# ProjV1.net
KiCad netlist of a schematic drawn in EAGLE
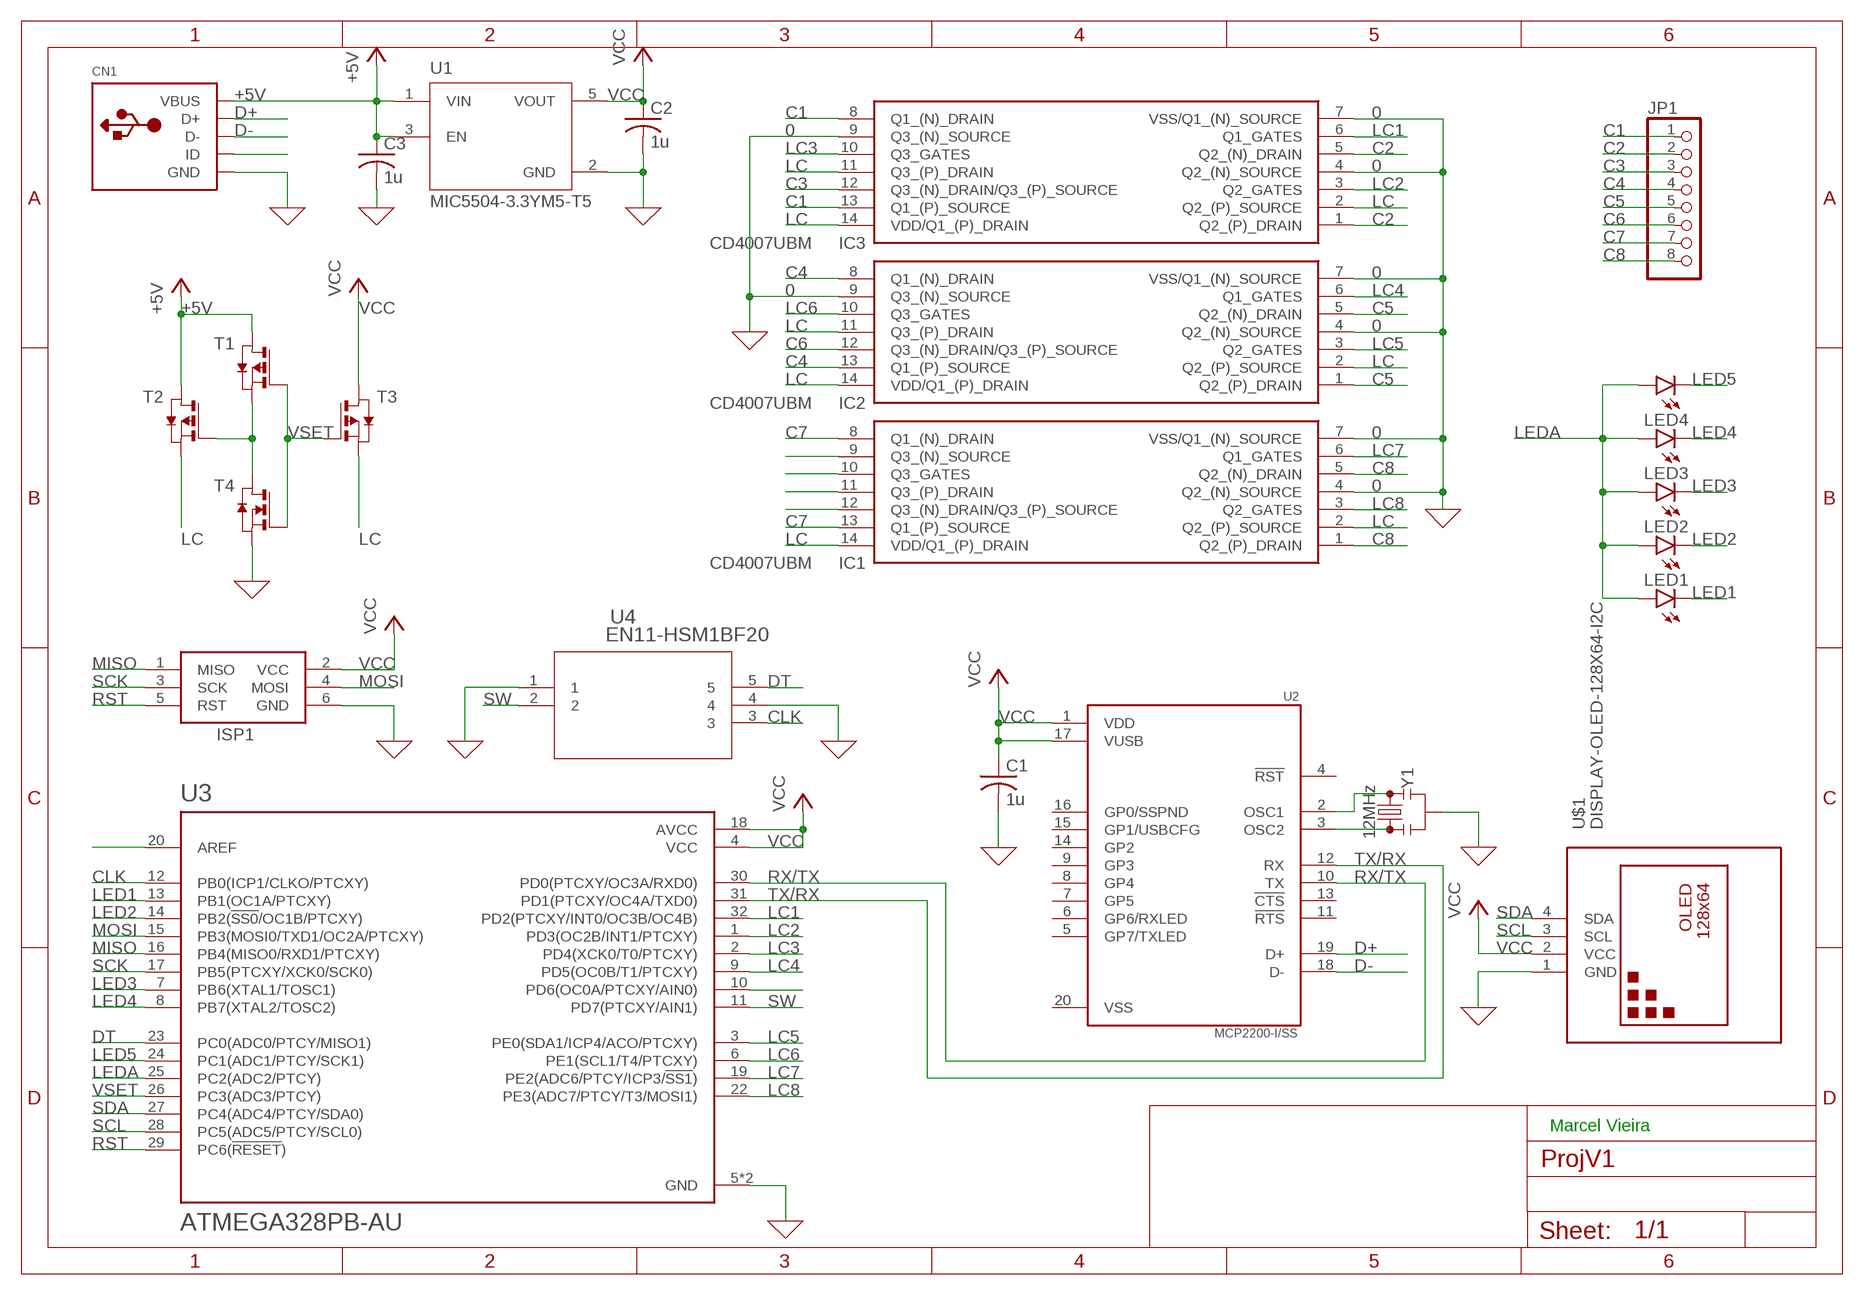
[diagram p0: schematic, sheet 1]

(export (version "E")
  (design (tool "Eeschema 10.0.6"))
  (components
    (comp (ref "C1")
      (value "1u")
      (footprint "eagle-import:C0805")
      (libsource (lib "eagle-import") (part "C-USC0805"))
    )
    (comp (ref "C2")
      (value "1u")
      (footprint "eagle-import:C0805")
      (libsource (lib "eagle-import") (part "C-USC0805"))
    )
    (comp (ref "C3")
      (value "1u")
      (footprint "eagle-import:C0805")
      (libsource (lib "eagle-import") (part "C-USC0805"))
    )
    (comp (ref "CN1")
      (value "USBMINIB")
      (footprint "eagle-import:USB-MINIB")
      (libsource (lib "eagle-import") (part "USBMINIB"))
    )
    (comp (ref "IC1")
      (value "CD4007UBM")
      (footprint "eagle-import:SOIC127P600X175-14N")
      (fields (field (name "MOUSER_PART_NUMBER") "595-CD4007UBM"))
      (libsource (lib "eagle-import") (part "CD4007UBM"))
    )
    (comp (ref "IC2")
      (value "CD4007UBM")
      (footprint "eagle-import:SOIC127P600X175-14N")
      (fields (field (name "MOUSER_PART_NUMBER") "595-CD4007UBM"))
      (libsource (lib "eagle-import") (part "CD4007UBM"))
    )
    (comp (ref "IC3")
      (value "CD4007UBM")
      (footprint "eagle-import:SOIC127P600X175-14N")
      (fields (field (name "MOUSER_PART_NUMBER") "595-CD4007UBM"))
      (libsource (lib "eagle-import") (part "CD4007UBM"))
    )
    (comp (ref "ISP1")
      (value "AVRISP-6")
      (footprint "eagle-import:AVRISP")
      (libsource (lib "eagle-import") (part "AVRISP-6"))
    )
    (comp (ref "JP1")
      (value "PINHD-1X8-3.5MM")
      (footprint "eagle-import:1X08-3.5MM")
      (libsource (lib "eagle-import") (part "PINHD-1X8-3.5MM"))
    )
    (comp (ref "LED1")
      (value "LEDCHIP-LED0805")
      (footprint "eagle-import:CHIP-LED0805")
      (libsource (lib "eagle-import") (part "LEDCHIP-LED0805"))
    )
    (comp (ref "LED2")
      (value "LEDCHIP-LED0805")
      (footprint "eagle-import:CHIP-LED0805")
      (libsource (lib "eagle-import") (part "LEDCHIP-LED0805"))
    )
    (comp (ref "LED3")
      (value "LEDCHIP-LED0805")
      (footprint "eagle-import:CHIP-LED0805")
      (libsource (lib "eagle-import") (part "LEDCHIP-LED0805"))
    )
    (comp (ref "LED4")
      (value "LEDCHIP-LED0805")
      (footprint "eagle-import:CHIP-LED0805")
      (libsource (lib "eagle-import") (part "LEDCHIP-LED0805"))
    )
    (comp (ref "LED5")
      (value "LEDCHIP-LED0805")
      (footprint "eagle-import:CHIP-LED0805")
      (libsource (lib "eagle-import") (part "LEDCHIP-LED0805"))
    )
    (comp (ref "T1")
      (value "PMOSSOT23")
      (footprint "eagle-import:SOT-23")
      (libsource (lib "eagle-import") (part "PMOSSOT23"))
    )
    (comp (ref "T2")
      (value "PMOSSOT23")
      (footprint "eagle-import:SOT-23")
      (libsource (lib "eagle-import") (part "PMOSSOT23"))
    )
    (comp (ref "T3")
      (value "PMOSSOT23")
      (footprint "eagle-import:SOT-23")
      (libsource (lib "eagle-import") (part "PMOSSOT23"))
    )
    (comp (ref "T4")
      (value "NMOSSOT23")
      (footprint "eagle-import:SOT-23")
      (libsource (lib "eagle-import") (part "NMOSSOT23"))
    )
    (comp (ref "U$1")
      (value "DISPLAY-OLED-128X64-I2C")
      (footprint "eagle-import:DISPLAY-OLED-128X64-I2C")
      (libsource (lib "eagle-import") (part "DISPLAY-OLED-128X64-I2C"))
    )
    (comp (ref "U1")
      (value "MIC5504-3.3YM5-T5")
      (footprint "eagle-import:SOT95P280X145-5N")
      (fields (field (name "MF") "Microchip"))
      (libsource (lib "eagle-import") (part "MIC5504-3.3YM5-T5"))
    )
    (comp (ref "U2")
      (value "MCP2200-I/SS")
      (footprint "eagle-import:SOP65P780X200-20N")
      (fields (field (name "MF") "Microchip"))
      (libsource (lib "eagle-import") (part "MCP2200-I/SS"))
    )
    (comp (ref "U3")
      (value "ATMEGA328PB-AU")
      (footprint "eagle-import:QFP80P900X900X120-32N")
      (fields (field (name "MF") "Microchip Technology / Atmel"))
      (libsource (lib "eagle-import") (part "ATMEGA328PB-AU"))
    )
    (comp (ref "U4")
      (value "EN11-HSM1BF20")
      (footprint "eagle-import:EN11-HSM_TTE")
      (libsource (lib "eagle-import") (part "EN11-HSM1BF20"))
    )
    (comp (ref "Y1")
      (value "12MHz")
      (footprint "eagle-import:RESONATOR-SMD-3.2X1.3")
      (libsource (lib "eagle-import") (part "RESONATOR-16MHZSMD_3.2X1.3"))
    )
  )
  (nets
    (net (code "1") (name "+5V") (class "Default")
      (node (ref "C3") (pin "1") (pinfunction "1_1") (pintype "passive"))
      (node (ref "CN1") (pin "VBUS") (pinfunction "VBUS_VBUS") (pintype "power_in"))
      (node (ref "T1") (pin "1") (pinfunction "D_1") (pintype "passive"))
      (node (ref "T2") (pin "1") (pinfunction "D_1") (pintype "passive"))
      (node (ref "U1") (pin "1") (pinfunction "VIN_1") (pintype "input"))
      (node (ref "U1") (pin "3") (pinfunction "EN_3") (pintype "input"))
    )
    (net (code "2") (name "/C1") (class "Default")
      (node (ref "IC3") (pin "13") (pinfunction "Q1_(P)_SOURCE_13") (pintype "bidirectional"))
      (node (ref "IC3") (pin "8") (pinfunction "Q1_(N)_DRAIN_8") (pintype "bidirectional"))
      (node (ref "JP1") (pin "1") (pinfunction "1_1") (pintype "passive"))
    )
    (net (code "3") (name "/C2") (class "Default")
      (node (ref "IC3") (pin "1") (pinfunction "Q2_(P)_DRAIN_1") (pintype "bidirectional"))
      (node (ref "IC3") (pin "5") (pinfunction "Q2_(N)_DRAIN_5") (pintype "bidirectional"))
      (node (ref "JP1") (pin "2") (pinfunction "2_2") (pintype "passive"))
    )
    (net (code "4") (name "/C3") (class "Default")
      (node (ref "IC3") (pin "12") (pinfunction "Q3_(N)_DRAIN/Q3_(P)_SOURCE_12") (pintype "bidirectional"))
      (node (ref "JP1") (pin "3") (pinfunction "3_3") (pintype "passive"))
    )
    (net (code "5") (name "/C4") (class "Default")
      (node (ref "IC2") (pin "13") (pinfunction "Q1_(P)_SOURCE_13") (pintype "bidirectional"))
      (node (ref "IC2") (pin "8") (pinfunction "Q1_(N)_DRAIN_8") (pintype "bidirectional"))
      (node (ref "JP1") (pin "4") (pinfunction "4_4") (pintype "passive"))
    )
    (net (code "6") (name "/C5") (class "Default")
      (node (ref "IC2") (pin "1") (pinfunction "Q2_(P)_DRAIN_1") (pintype "bidirectional"))
      (node (ref "IC2") (pin "5") (pinfunction "Q2_(N)_DRAIN_5") (pintype "bidirectional"))
      (node (ref "JP1") (pin "5") (pinfunction "5_5") (pintype "passive"))
    )
    (net (code "7") (name "/C6") (class "Default")
      (node (ref "IC2") (pin "12") (pinfunction "Q3_(N)_DRAIN/Q3_(P)_SOURCE_12") (pintype "bidirectional"))
      (node (ref "JP1") (pin "6") (pinfunction "6_6") (pintype "passive"))
    )
    (net (code "8") (name "/C7") (class "Default")
      (node (ref "IC1") (pin "13") (pinfunction "Q1_(P)_SOURCE_13") (pintype "bidirectional"))
      (node (ref "IC1") (pin "8") (pinfunction "Q1_(N)_DRAIN_8") (pintype "bidirectional"))
      (node (ref "JP1") (pin "7") (pinfunction "7_7") (pintype "passive"))
    )
    (net (code "9") (name "/C8") (class "Default")
      (node (ref "IC1") (pin "1") (pinfunction "Q2_(P)_DRAIN_1") (pintype "bidirectional"))
      (node (ref "IC1") (pin "5") (pinfunction "Q2_(N)_DRAIN_5") (pintype "bidirectional"))
      (node (ref "JP1") (pin "8") (pinfunction "8_8") (pintype "passive"))
    )
    (net (code "10") (name "/CLK") (class "Default")
      (node (ref "U3") (pin "12") (pinfunction "PB0(ICP1/CLKO/PTCXY)_12") (pintype "bidirectional"))
      (node (ref "U4") (pin "3") (pinfunction "3_3") (pintype "passive"))
    )
    (net (code "11") (name "/D+") (class "Default")
      (node (ref "CN1") (pin "D+") (pinfunction "D+_D+") (pintype "bidirectional"))
      (node (ref "U2") (pin "19") (pinfunction "D+_19") (pintype "bidirectional"))
    )
    (net (code "12") (name "/D-") (class "Default")
      (node (ref "CN1") (pin "D-") (pinfunction "D-_D-") (pintype "bidirectional"))
      (node (ref "U2") (pin "18") (pinfunction "D-_18") (pintype "bidirectional"))
    )
    (net (code "13") (name "/DT") (class "Default")
      (node (ref "U3") (pin "23") (pinfunction "PC0(ADC0/PTCY/MISO1)_23") (pintype "bidirectional"))
      (node (ref "U4") (pin "5") (pinfunction "5_5") (pintype "passive"))
    )
    (net (code "14") (name "/LC") (class "Default")
      (node (ref "IC1") (pin "14") (pinfunction "VDD/Q1_(P)_DRAIN_14") (pintype "bidirectional"))
      (node (ref "IC1") (pin "2") (pinfunction "Q2_(P)_SOURCE_2") (pintype "bidirectional"))
      (node (ref "IC2") (pin "11") (pinfunction "Q3_(P)_DRAIN_11") (pintype "bidirectional"))
      (node (ref "IC2") (pin "14") (pinfunction "VDD/Q1_(P)_DRAIN_14") (pintype "bidirectional"))
      (node (ref "IC2") (pin "2") (pinfunction "Q2_(P)_SOURCE_2") (pintype "bidirectional"))
      (node (ref "IC3") (pin "11") (pinfunction "Q3_(P)_DRAIN_11") (pintype "bidirectional"))
      (node (ref "IC3") (pin "14") (pinfunction "VDD/Q1_(P)_DRAIN_14") (pintype "bidirectional"))
      (node (ref "IC3") (pin "2") (pinfunction "Q2_(P)_SOURCE_2") (pintype "bidirectional"))
      (node (ref "T2") (pin "2") (pinfunction "S_2") (pintype "passive"))
      (node (ref "T3") (pin "2") (pinfunction "S_2") (pintype "passive"))
    )
    (net (code "15") (name "/LC1") (class "Default")
      (node (ref "IC3") (pin "6") (pinfunction "Q1_GATES_6") (pintype "bidirectional"))
      (node (ref "U3") (pin "32") (pinfunction "PD2(PTCXY/INT0/OC3B/OC4B)_32") (pintype "bidirectional"))
    )
    (net (code "16") (name "/LC2") (class "Default")
      (node (ref "IC3") (pin "3") (pinfunction "Q2_GATES_3") (pintype "bidirectional"))
      (node (ref "U3") (pin "1") (pinfunction "PD3(OC2B/INT1/PTCXY)_1") (pintype "bidirectional"))
    )
    (net (code "17") (name "/LC3") (class "Default")
      (node (ref "IC3") (pin "10") (pinfunction "Q3_GATES_10") (pintype "bidirectional"))
      (node (ref "U3") (pin "2") (pinfunction "PD4(XCK0/T0/PTCXY)_2") (pintype "bidirectional"))
    )
    (net (code "18") (name "/LC4") (class "Default")
      (node (ref "IC2") (pin "6") (pinfunction "Q1_GATES_6") (pintype "bidirectional"))
      (node (ref "U3") (pin "9") (pinfunction "PD5(OC0B/T1/PTCXY)_9") (pintype "bidirectional"))
    )
    (net (code "19") (name "/LC5") (class "Default")
      (node (ref "IC2") (pin "3") (pinfunction "Q2_GATES_3") (pintype "bidirectional"))
      (node (ref "U3") (pin "3") (pinfunction "PE0(SDA1/ICP4/ACO/PTCXY)_3") (pintype "bidirectional"))
    )
    (net (code "20") (name "/LC6") (class "Default")
      (node (ref "IC2") (pin "10") (pinfunction "Q3_GATES_10") (pintype "bidirectional"))
      (node (ref "U3") (pin "6") (pinfunction "PE1(SCL1/T4/PTCXY)_6") (pintype "bidirectional"))
    )
    (net (code "21") (name "/LC7") (class "Default")
      (node (ref "IC1") (pin "6") (pinfunction "Q1_GATES_6") (pintype "bidirectional"))
      (node (ref "U3") (pin "19") (pinfunction "PE2(ADC6/PTCY/ICP3/~{SS1})_19") (pintype "bidirectional"))
    )
    (net (code "22") (name "/LC8") (class "Default")
      (node (ref "IC1") (pin "3") (pinfunction "Q2_GATES_3") (pintype "bidirectional"))
      (node (ref "U3") (pin "22") (pinfunction "PE3(ADC7/PTCY/T3/MOSI1)_22") (pintype "bidirectional"))
    )
    (net (code "23") (name "/LED1") (class "Default")
      (node (ref "LED1") (pin "C") (pinfunction "C_C") (pintype "passive"))
      (node (ref "U3") (pin "13") (pinfunction "PB1(OC1A/PTCXY)_13") (pintype "bidirectional"))
    )
    (net (code "24") (name "/LED2") (class "Default")
      (node (ref "LED2") (pin "C") (pinfunction "C_C") (pintype "passive"))
      (node (ref "U3") (pin "14") (pinfunction "PB2(~{SS0}/OC1B/PTCXY)_14") (pintype "bidirectional"))
    )
    (net (code "25") (name "/LED3") (class "Default")
      (node (ref "LED3") (pin "C") (pinfunction "C_C") (pintype "passive"))
      (node (ref "U3") (pin "7") (pinfunction "PB6(XTAL1/TOSC1)_7") (pintype "bidirectional"))
    )
    (net (code "26") (name "/LED4") (class "Default")
      (node (ref "LED4") (pin "C") (pinfunction "C_C") (pintype "passive"))
      (node (ref "U3") (pin "8") (pinfunction "PB7(XTAL2/TOSC2)_8") (pintype "bidirectional"))
    )
    (net (code "27") (name "/LED5") (class "Default")
      (node (ref "LED5") (pin "C") (pinfunction "C_C") (pintype "passive"))
      (node (ref "U3") (pin "24") (pinfunction "PC1(ADC1/PTCY/SCK1)_24") (pintype "bidirectional"))
    )
    (net (code "28") (name "/LEDA") (class "Default")
      (node (ref "LED1") (pin "A") (pinfunction "A_A") (pintype "passive"))
      (node (ref "LED2") (pin "A") (pinfunction "A_A") (pintype "passive"))
      (node (ref "LED3") (pin "A") (pinfunction "A_A") (pintype "passive"))
      (node (ref "LED4") (pin "A") (pinfunction "A_A") (pintype "passive"))
      (node (ref "LED5") (pin "A") (pinfunction "A_A") (pintype "passive"))
      (node (ref "U3") (pin "25") (pinfunction "PC2(ADC2/PTCY)_25") (pintype "bidirectional"))
    )
    (net (code "29") (name "/MISO") (class "Default")
      (node (ref "ISP1") (pin "1") (pinfunction "MISO_1") (pintype "input"))
      (node (ref "U3") (pin "16") (pinfunction "PB4(MISO0/RXD1/PTCXY)_16") (pintype "bidirectional"))
    )
    (net (code "30") (name "/MOSI") (class "Default")
      (node (ref "ISP1") (pin "4") (pinfunction "MOSI_4") (pintype "output"))
      (node (ref "U3") (pin "15") (pinfunction "PB3(MOSI0/TXD1/OC2A/PTCXY)_15") (pintype "bidirectional"))
    )
    (net (code "31") (name "/RST") (class "Default")
      (node (ref "ISP1") (pin "5") (pinfunction "RST_5") (pintype "output"))
      (node (ref "U3") (pin "29") (pinfunction "PC6(~{RESET})_29") (pintype "bidirectional"))
    )
    (net (code "32") (name "/RX{slash}TX") (class "Default")
      (node (ref "U2") (pin "10") (pinfunction "TX_10") (pintype "output"))
      (node (ref "U3") (pin "30") (pinfunction "PD0(PTCXY/OC3A/RXD0)_30") (pintype "bidirectional"))
    )
    (net (code "33") (name "/SCK") (class "Default")
      (node (ref "ISP1") (pin "3") (pinfunction "SCK_3") (pintype "output"))
      (node (ref "U3") (pin "17") (pinfunction "PB5(PTCXY/XCK0/SCK0)_17") (pintype "bidirectional"))
    )
    (net (code "34") (name "/SCL") (class "Default")
      (node (ref "U$1") (pin "3") (pinfunction "SCL_3") (pintype "bidirectional"))
      (node (ref "U3") (pin "28") (pinfunction "PC5(ADC5/PTCY/SCL0)_28") (pintype "bidirectional"))
    )
    (net (code "35") (name "/SDA") (class "Default")
      (node (ref "U$1") (pin "4") (pinfunction "SDA_4") (pintype "bidirectional"))
      (node (ref "U3") (pin "27") (pinfunction "PC4(ADC4/PTCY/SDA0)_27") (pintype "bidirectional"))
    )
    (net (code "36") (name "/SW") (class "Default")
      (node (ref "U3") (pin "11") (pinfunction "PD7(PTCXY/AIN1)_11") (pintype "bidirectional"))
      (node (ref "U4") (pin "2") (pinfunction "2_2") (pintype "passive"))
    )
    (net (code "37") (name "/TX{slash}RX") (class "Default")
      (node (ref "U2") (pin "12") (pinfunction "RX_12") (pintype "input"))
      (node (ref "U3") (pin "31") (pinfunction "PD1(PTCXY/OC4A/TXD0)_31") (pintype "bidirectional"))
    )
    (net (code "38") (name "/VSET") (class "Default")
      (node (ref "T1") (pin "3") (pinfunction "G_3") (pintype "passive"))
      (node (ref "T3") (pin "3") (pinfunction "G_3") (pintype "passive"))
      (node (ref "T4") (pin "3") (pinfunction "G_3") (pintype "passive"))
      (node (ref "U3") (pin "26") (pinfunction "PC3(ADC3/PTCY)_26") (pintype "bidirectional"))
    )
    (net (code "39") (name "/VSS") (class "Default")
      (node (ref "U2") (pin "20") (pinfunction "VSS_20") (pintype "power_in"))
    )
    (net (code "40") (name "GND") (class "Default")
      (node (ref "C1") (pin "2") (pinfunction "2_2") (pintype "passive"))
      (node (ref "C2") (pin "2") (pinfunction "2_2") (pintype "passive"))
      (node (ref "C3") (pin "2") (pinfunction "2_2") (pintype "passive"))
      (node (ref "CN1") (pin "GND") (pinfunction "GND_GND") (pintype "power_in"))
      (node (ref "IC1") (pin "4") (pinfunction "Q2_(N)_SOURCE_4") (pintype "bidirectional"))
      (node (ref "IC1") (pin "7") (pinfunction "VSS/Q1_(N)_SOURCE_7") (pintype "bidirectional"))
      (node (ref "IC2") (pin "4") (pinfunction "Q2_(N)_SOURCE_4") (pintype "bidirectional"))
      (node (ref "IC2") (pin "7") (pinfunction "VSS/Q1_(N)_SOURCE_7") (pintype "bidirectional"))
      (node (ref "IC2") (pin "9") (pinfunction "Q3_(N)_SOURCE_9") (pintype "bidirectional"))
      (node (ref "IC3") (pin "4") (pinfunction "Q2_(N)_SOURCE_4") (pintype "bidirectional"))
      (node (ref "IC3") (pin "7") (pinfunction "VSS/Q1_(N)_SOURCE_7") (pintype "bidirectional"))
      (node (ref "IC3") (pin "9") (pinfunction "Q3_(N)_SOURCE_9") (pintype "bidirectional"))
      (node (ref "ISP1") (pin "6") (pinfunction "GND_6") (pintype "power_in"))
      (node (ref "T4") (pin "2") (pinfunction "S_2") (pintype "passive"))
      (node (ref "U$1") (pin "1") (pinfunction "GND_1") (pintype "power_in"))
      (node (ref "U1") (pin "2") (pinfunction "GND_2") (pintype "power_in"))
      (node (ref "U3") (pin "21") (pinfunction "GND_21") (pintype "power_in"))
      (node (ref "U3") (pin "5") (pinfunction "GND_5") (pintype "power_in"))
      (node (ref "U4") (pin "1") (pinfunction "1_1") (pintype "passive"))
      (node (ref "U4") (pin "4") (pinfunction "4_4") (pintype "passive"))
      (node (ref "Y1") (pin "2") (pinfunction "2_2") (pintype "passive"))
    )
    (net (code "41") (name "Net-(T1-S)") (class "Default")
      (node (ref "T1") (pin "2") (pinfunction "S_2") (pintype "passive"))
      (node (ref "T2") (pin "3") (pinfunction "G_3") (pintype "passive"))
      (node (ref "T4") (pin "1") (pinfunction "D_1") (pintype "passive"))
    )
    (net (code "42") (name "Net-(U2-OSC1)") (class "Default")
      (node (ref "U2") (pin "2") (pinfunction "OSC1_2") (pintype "input"))
      (node (ref "Y1") (pin "1") (pinfunction "1_1") (pintype "passive"))
    )
    (net (code "43") (name "Net-(U2-OSC2)") (class "Default")
      (node (ref "U2") (pin "3") (pinfunction "OSC2_3") (pintype "output"))
      (node (ref "Y1") (pin "3") (pinfunction "3_3") (pintype "passive"))
    )
    (net (code "44") (name "VCC") (class "Default")
      (node (ref "C1") (pin "1") (pinfunction "1_1") (pintype "passive"))
      (node (ref "C2") (pin "1") (pinfunction "1_1") (pintype "passive"))
      (node (ref "ISP1") (pin "2") (pinfunction "VCC_2") (pintype "power_in"))
      (node (ref "T3") (pin "1") (pinfunction "D_1") (pintype "passive"))
      (node (ref "U$1") (pin "2") (pinfunction "VCC_2") (pintype "power_in"))
      (node (ref "U1") (pin "5") (pinfunction "VOUT_5") (pintype "output"))
      (node (ref "U2") (pin "1") (pinfunction "VDD_1") (pintype "power_in"))
      (node (ref "U2") (pin "17") (pinfunction "VUSB_17") (pintype "power_in"))
      (node (ref "U3") (pin "18") (pinfunction "AVCC_18") (pintype "power_in"))
      (node (ref "U3") (pin "4") (pinfunction "VCC_4") (pintype "power_in"))
    )
    (net (code "45") (name "unconnected-(CN1-PadID)") (class "Default")
      (node (ref "CN1") (pin "ID") (pinfunction "ID_ID") (pintype "bidirectional"))
    )
    (net (code "46") (name "unconnected-(IC1-Q3_(N)_DRAIN{slash}Q3_(P)_SOURCE-Pad12)") (class "Default")
      (node (ref "IC1") (pin "12") (pinfunction "Q3_(N)_DRAIN/Q3_(P)_SOURCE_12") (pintype "bidirectional"))
    )
    (net (code "47") (name "unconnected-(IC1-Q3_(N)_SOURCE-Pad9)") (class "Default")
      (node (ref "IC1") (pin "9") (pinfunction "Q3_(N)_SOURCE_9") (pintype "bidirectional"))
    )
    (net (code "48") (name "unconnected-(IC1-Q3_(P)_DRAIN-Pad11)") (class "Default")
      (node (ref "IC1") (pin "11") (pinfunction "Q3_(P)_DRAIN_11") (pintype "bidirectional"))
    )
    (net (code "49") (name "unconnected-(IC1-Q3_GATES-Pad10)") (class "Default")
      (node (ref "IC1") (pin "10") (pinfunction "Q3_GATES_10") (pintype "bidirectional"))
    )
    (net (code "50") (name "unconnected-(U2-GP0{slash}SSPND-Pad16)") (class "Default")
      (node (ref "U2") (pin "16") (pinfunction "GP0/SSPND_16") (pintype "bidirectional"))
    )
    (net (code "51") (name "unconnected-(U2-GP1{slash}USBCFG-Pad15)") (class "Default")
      (node (ref "U2") (pin "15") (pinfunction "GP1/USBCFG_15") (pintype "bidirectional"))
    )
    (net (code "52") (name "unconnected-(U2-GP2-Pad14)") (class "Default")
      (node (ref "U2") (pin "14") (pinfunction "GP2_14") (pintype "bidirectional"))
    )
    (net (code "53") (name "unconnected-(U2-GP3-Pad9)") (class "Default")
      (node (ref "U2") (pin "9") (pinfunction "GP3_9") (pintype "bidirectional"))
    )
    (net (code "54") (name "unconnected-(U2-GP4-Pad8)") (class "Default")
      (node (ref "U2") (pin "8") (pinfunction "GP4_8") (pintype "bidirectional"))
    )
    (net (code "55") (name "unconnected-(U2-GP5-Pad7)") (class "Default")
      (node (ref "U2") (pin "7") (pinfunction "GP5_7") (pintype "bidirectional"))
    )
    (net (code "56") (name "unconnected-(U2-GP6{slash}RXLED-Pad6)") (class "Default")
      (node (ref "U2") (pin "6") (pinfunction "GP6/RXLED_6") (pintype "bidirectional"))
    )
    (net (code "57") (name "unconnected-(U2-GP7{slash}TXLED-Pad5)") (class "Default")
      (node (ref "U2") (pin "5") (pinfunction "GP7/TXLED_5") (pintype "bidirectional"))
    )
    (net (code "58") (name "unconnected-(U2-~{CTS}-Pad13)") (class "Default")
      (node (ref "U2") (pin "13") (pinfunction "~{CTS}_13") (pintype "input"))
    )
    (net (code "59") (name "unconnected-(U2-~{RST}-Pad4)") (class "Default")
      (node (ref "U2") (pin "4") (pinfunction "~{RST}_4") (pintype "input"))
    )
    (net (code "60") (name "unconnected-(U2-~{RTS}-Pad11)") (class "Default")
      (node (ref "U2") (pin "11") (pinfunction "~{RTS}_11") (pintype "output"))
    )
    (net (code "61") (name "unconnected-(U3-AREF-Pad20)") (class "Default")
      (node (ref "U3") (pin "20") (pinfunction "AREF_20") (pintype "input"))
    )
    (net (code "62") (name "unconnected-(U3-PD6(OC0A{slash}PTCXY{slash}AIN0)-Pad10)") (class "Default")
      (node (ref "U3") (pin "10") (pinfunction "PD6(OC0A/PTCXY/AIN0)_10") (pintype "bidirectional"))
    )
  )
)
